# sensor.net
KiCad netlist of a schematic drawn in EAGLE
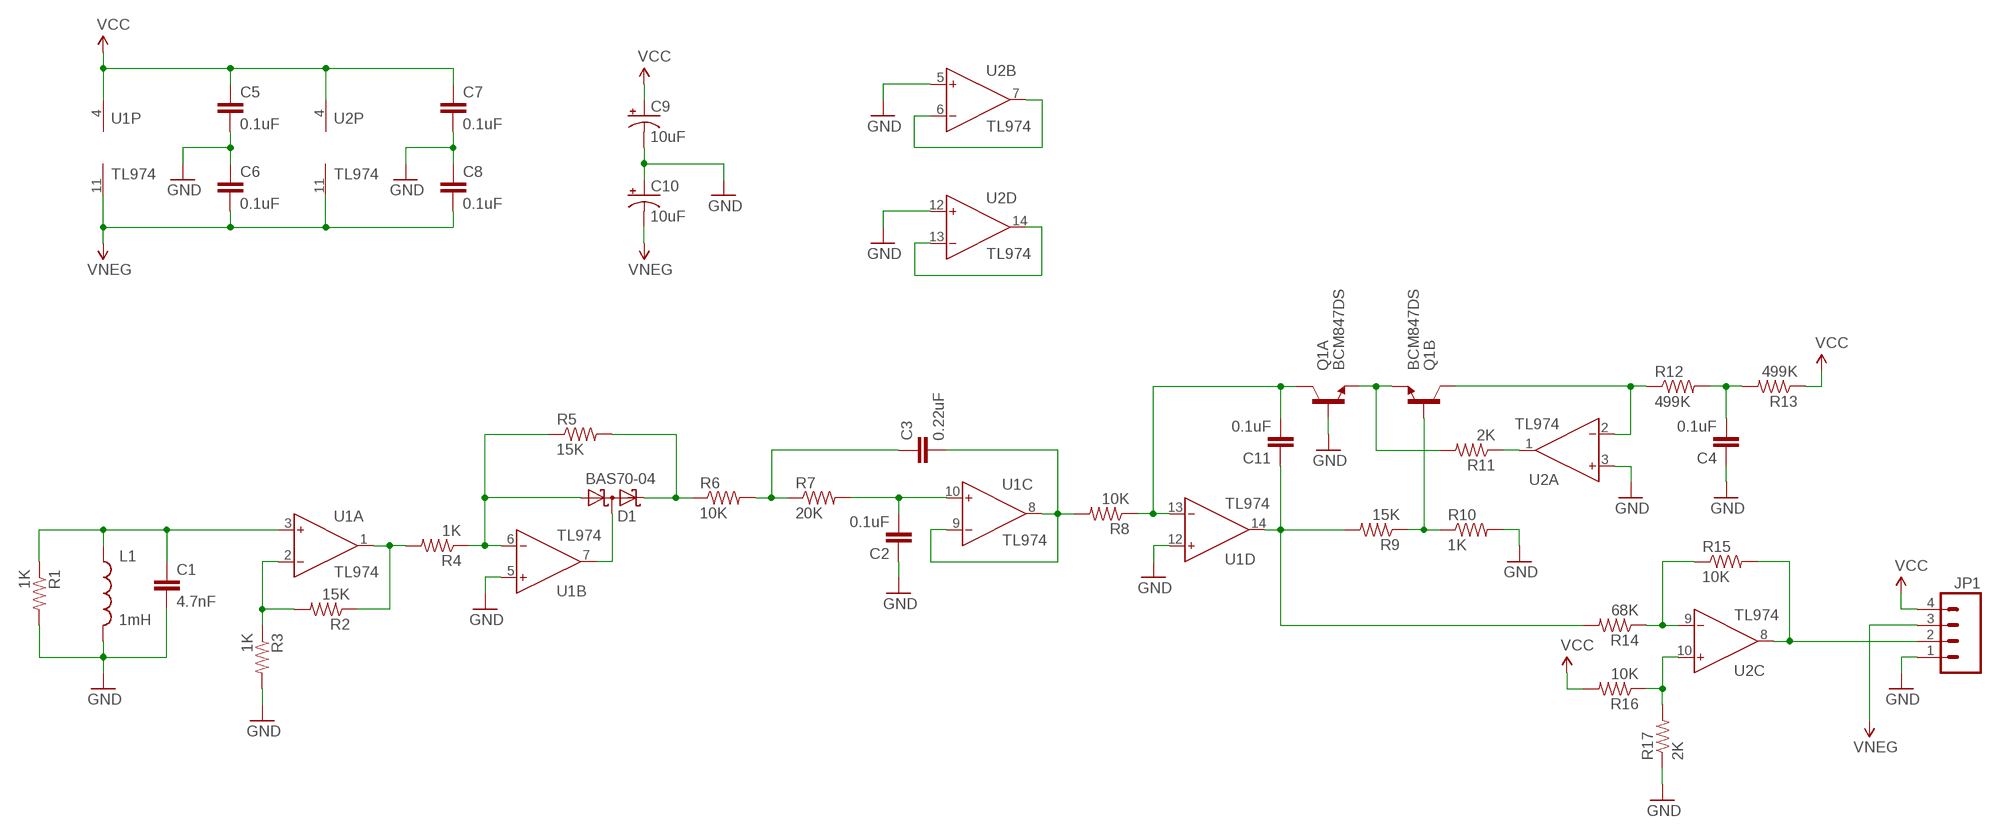
[diagram p0: schematic, sheet 1]

(export (version "E")
  (design (tool "Eeschema 10.0.6"))
  (components
    (comp (ref "C1")
      (value "4.7nF")
      (footprint "eagle-import:0805")
      (libsource (lib "eagle-import") (part "CAP0805"))
    )
    (comp (ref "C2")
      (value "0.1uF")
      (footprint "eagle-import:0805")
      (libsource (lib "eagle-import") (part "CAP0805"))
    )
    (comp (ref "C3")
      (value "0.22uF")
      (footprint "eagle-import:0805")
      (libsource (lib "eagle-import") (part "CAP0805"))
    )
    (comp (ref "C4")
      (value "0.1uF")
      (footprint "eagle-import:0805")
      (libsource (lib "eagle-import") (part "CAP0805"))
    )
    (comp (ref "C5")
      (value "0.1uF")
      (footprint "eagle-import:0805")
      (libsource (lib "eagle-import") (part "CAP0805"))
    )
    (comp (ref "C6")
      (value "0.1uF")
      (footprint "eagle-import:0805")
      (libsource (lib "eagle-import") (part "CAP0805"))
    )
    (comp (ref "C7")
      (value "0.1uF")
      (footprint "eagle-import:0805")
      (libsource (lib "eagle-import") (part "CAP0805"))
    )
    (comp (ref "C8")
      (value "0.1uF")
      (footprint "eagle-import:0805")
      (libsource (lib "eagle-import") (part "CAP0805"))
    )
    (comp (ref "C9")
      (value "10uF")
      (footprint "eagle-import:E2-4")
      (libsource (lib "eagle-import") (part "CPOL-USE2-4"))
    )
    (comp (ref "C10")
      (value "10uF")
      (footprint "eagle-import:E2-4")
      (libsource (lib "eagle-import") (part "CPOL-USE2-4"))
    )
    (comp (ref "C11")
      (value "0.1uF")
      (footprint "eagle-import:0805")
      (libsource (lib "eagle-import") (part "CAP0805"))
    )
    (comp (ref "D1")
      (value "BAS70-04")
      (footprint "eagle-import:SOT23")
      (libsource (lib "eagle-import") (part "BAS70-04"))
    )
    (comp (ref "JP1")
      (value "M04POLAR_LOCK")
      (footprint "eagle-import:MOLEX-1X4_LOCK")
      (libsource (lib "eagle-import") (part "M04POLAR_LOCK"))
    )
    (comp (ref "L1")
      (value "1mH")
      (footprint "eagle-import:RLB0912")
      (libsource (lib "eagle-import") (part "INDUCTORRLB0912"))
    )
    (comp (ref "Q1")
      (value "BCM847DS")
      (footprint "eagle-import:SOT-457")
      (libsource (lib "eagle-import") (part "BCM847DS"))
    )
    (comp (ref "R1")
      (value "1K")
      (footprint "eagle-import:0805")
      (libsource (lib "eagle-import") (part "RESISTOR0805-RES"))
    )
    (comp (ref "R2")
      (value "15K")
      (footprint "eagle-import:0805")
      (libsource (lib "eagle-import") (part "RESISTOR0805-RES"))
    )
    (comp (ref "R3")
      (value "1K")
      (footprint "eagle-import:0805")
      (libsource (lib "eagle-import") (part "RESISTOR0805-RES"))
    )
    (comp (ref "R4")
      (value "1K")
      (footprint "eagle-import:0805")
      (libsource (lib "eagle-import") (part "RESISTOR0805-RES"))
    )
    (comp (ref "R5")
      (value "15K")
      (footprint "eagle-import:0805")
      (libsource (lib "eagle-import") (part "RESISTOR0805-RES"))
    )
    (comp (ref "R6")
      (value "10K")
      (footprint "eagle-import:0805")
      (libsource (lib "eagle-import") (part "RESISTOR0805-RES"))
    )
    (comp (ref "R7")
      (value "20K")
      (footprint "eagle-import:0805")
      (libsource (lib "eagle-import") (part "RESISTOR0805-RES"))
    )
    (comp (ref "R8")
      (value "10K")
      (footprint "eagle-import:0805")
      (libsource (lib "eagle-import") (part "RESISTOR0805-RES"))
    )
    (comp (ref "R9")
      (value "15K")
      (footprint "eagle-import:0805")
      (libsource (lib "eagle-import") (part "RESISTOR0805-RES"))
    )
    (comp (ref "R10")
      (value "1K")
      (footprint "eagle-import:0805")
      (libsource (lib "eagle-import") (part "RESISTOR0805-RES"))
    )
    (comp (ref "R11")
      (value "2K")
      (footprint "eagle-import:0805")
      (libsource (lib "eagle-import") (part "RESISTOR0805-RES"))
    )
    (comp (ref "R12")
      (value "499K")
      (footprint "eagle-import:0805")
      (libsource (lib "eagle-import") (part "RESISTOR0805-RES"))
    )
    (comp (ref "R13")
      (value "499K")
      (footprint "eagle-import:0805")
      (libsource (lib "eagle-import") (part "RESISTOR0805-RES"))
    )
    (comp (ref "R14")
      (value "68K")
      (footprint "eagle-import:0805")
      (libsource (lib "eagle-import") (part "RESISTOR0805-RES"))
    )
    (comp (ref "R15")
      (value "10K")
      (footprint "eagle-import:0805")
      (libsource (lib "eagle-import") (part "RESISTOR0805-RES"))
    )
    (comp (ref "R16")
      (value "10K")
      (footprint "eagle-import:0805")
      (libsource (lib "eagle-import") (part "RESISTOR0805-RES"))
    )
    (comp (ref "R17")
      (value "2K")
      (footprint "eagle-import:0805")
      (libsource (lib "eagle-import") (part "RESISTOR0805-RES"))
    )
    (comp (ref "U1")
      (value "TL974")
      (footprint "eagle-import:SOIC-14")
      (libsource (lib "eagle-import") (part "TL974"))
    )
    (comp (ref "U2")
      (value "TL974")
      (footprint "eagle-import:SOIC-14")
      (libsource (lib "eagle-import") (part "TL974"))
    )
  )
  (nets
    (net (code "1") (name "GND") (class "Default")
      (node (ref "C1") (pin "2") (pinfunction "2_2") (pintype "passive"))
      (node (ref "C10") (pin "+") (pinfunction "+_+") (pintype "passive"))
      (node (ref "C2") (pin "1") (pinfunction "1_1") (pintype "passive"))
      (node (ref "C4") (pin "1") (pinfunction "1_1") (pintype "passive"))
      (node (ref "C5") (pin "2") (pinfunction "2_2") (pintype "passive"))
      (node (ref "C6") (pin "1") (pinfunction "1_1") (pintype "passive"))
      (node (ref "C7") (pin "2") (pinfunction "2_2") (pintype "passive"))
      (node (ref "C8") (pin "1") (pinfunction "1_1") (pintype "passive"))
      (node (ref "C9") (pin "-") (pinfunction "-_-") (pintype "passive"))
      (node (ref "JP1") (pin "1") (pinfunction "1_1") (pintype "passive"))
      (node (ref "L1") (pin "2") (pinfunction "2_2") (pintype "passive"))
      (node (ref "Q1") (pin "2") (pinfunction "B_2") (pintype "passive"))
      (node (ref "R1") (pin "2") (pinfunction "2_2") (pintype "passive"))
      (node (ref "R10") (pin "2") (pinfunction "2_2") (pintype "passive"))
      (node (ref "R17") (pin "1") (pinfunction "1_1") (pintype "passive"))
      (node (ref "R3") (pin "2") (pinfunction "2_2") (pintype "passive"))
      (node (ref "U1") (pin "12") (pinfunction "IN+_12") (pintype "input"))
      (node (ref "U1") (pin "5") (pinfunction "IN+_5") (pintype "input"))
      (node (ref "U2") (pin "12") (pinfunction "IN+_12") (pintype "input"))
      (node (ref "U2") (pin "3") (pinfunction "IN+_3") (pintype "input"))
      (node (ref "U2") (pin "5") (pinfunction "IN+_5") (pintype "input"))
    )
    (net (code "2") (name "Net-(C3-Pad1)") (class "Default")
      (node (ref "C3") (pin "1") (pinfunction "1_1") (pintype "passive"))
      (node (ref "R6") (pin "2") (pinfunction "2_2") (pintype "passive"))
      (node (ref "R7") (pin "1") (pinfunction "1_1") (pintype "passive"))
    )
    (net (code "3") (name "Net-(C4-Pad2)") (class "Default")
      (node (ref "C4") (pin "2") (pinfunction "2_2") (pintype "passive"))
      (node (ref "R12") (pin "2") (pinfunction "2_2") (pintype "passive"))
      (node (ref "R13") (pin "2") (pinfunction "2_2") (pintype "passive"))
    )
    (net (code "4") (name "Net-(D1-A1)") (class "Default")
      (node (ref "D1") (pin "1") (pinfunction "A1_1") (pintype "passive"))
      (node (ref "R4") (pin "1") (pinfunction "1_1") (pintype "passive"))
      (node (ref "R5") (pin "1") (pinfunction "1_1") (pintype "passive"))
      (node (ref "U1") (pin "6") (pinfunction "IN-_6") (pintype "input"))
    )
    (net (code "5") (name "Net-(D1-C1A2)") (class "Default")
      (node (ref "D1") (pin "3") (pinfunction "C1A2_3") (pintype "passive"))
      (node (ref "U1") (pin "7") (pinfunction "OUT_7") (pintype "output"))
    )
    (net (code "6") (name "Net-(D1-C2)") (class "Default")
      (node (ref "D1") (pin "2") (pinfunction "C2_2") (pintype "passive"))
      (node (ref "R5") (pin "2") (pinfunction "2_2") (pintype "passive"))
      (node (ref "R6") (pin "1") (pinfunction "1_1") (pintype "passive"))
    )
    (net (code "7") (name "Net-(Q1A-C)") (class "Default")
      (node (ref "C11") (pin "2") (pinfunction "2_2") (pintype "passive"))
      (node (ref "Q1") (pin "6") (pinfunction "C_6") (pintype "passive"))
      (node (ref "R8") (pin "1") (pinfunction "1_1") (pintype "passive"))
      (node (ref "U1") (pin "13") (pinfunction "IN-_13") (pintype "input"))
    )
    (net (code "8") (name "Net-(Q1A-E)") (class "Default")
      (node (ref "Q1") (pin "1") (pinfunction "E_1") (pintype "passive"))
      (node (ref "Q1") (pin "4") (pinfunction "E_4") (pintype "passive"))
      (node (ref "R11") (pin "2") (pinfunction "2_2") (pintype "passive"))
    )
    (net (code "9") (name "Net-(Q1B-B)") (class "Default")
      (node (ref "Q1") (pin "5") (pinfunction "B_5") (pintype "passive"))
      (node (ref "R10") (pin "1") (pinfunction "1_1") (pintype "passive"))
      (node (ref "R9") (pin "1") (pinfunction "1_1") (pintype "passive"))
    )
    (net (code "10") (name "Net-(Q1B-C)") (class "Default")
      (node (ref "Q1") (pin "3") (pinfunction "C_3") (pintype "passive"))
      (node (ref "R12") (pin "1") (pinfunction "1_1") (pintype "passive"))
      (node (ref "U2") (pin "2") (pinfunction "IN-_2") (pintype "input"))
    )
    (net (code "11") (name "Net-(U1A-IN+)") (class "Default")
      (node (ref "C1") (pin "1") (pinfunction "1_1") (pintype "passive"))
      (node (ref "L1") (pin "1") (pinfunction "1_1") (pintype "passive"))
      (node (ref "R1") (pin "1") (pinfunction "1_1") (pintype "passive"))
      (node (ref "U1") (pin "3") (pinfunction "IN+_3") (pintype "input"))
    )
    (net (code "12") (name "Net-(U1A-IN-)") (class "Default")
      (node (ref "R2") (pin "2") (pinfunction "2_2") (pintype "passive"))
      (node (ref "R3") (pin "1") (pinfunction "1_1") (pintype "passive"))
      (node (ref "U1") (pin "2") (pinfunction "IN-_2") (pintype "input"))
    )
    (net (code "13") (name "Net-(U1A-OUT)") (class "Default")
      (node (ref "R2") (pin "1") (pinfunction "1_1") (pintype "passive"))
      (node (ref "R4") (pin "2") (pinfunction "2_2") (pintype "passive"))
      (node (ref "U1") (pin "1") (pinfunction "OUT_1") (pintype "output"))
    )
    (net (code "14") (name "Net-(U1C-IN+)") (class "Default")
      (node (ref "C2") (pin "2") (pinfunction "2_2") (pintype "passive"))
      (node (ref "R7") (pin "2") (pinfunction "2_2") (pintype "passive"))
      (node (ref "U1") (pin "10") (pinfunction "IN+_10") (pintype "input"))
    )
    (net (code "15") (name "Net-(U1C-IN-)") (class "Default")
      (node (ref "C3") (pin "2") (pinfunction "2_2") (pintype "passive"))
      (node (ref "R8") (pin "2") (pinfunction "2_2") (pintype "passive"))
      (node (ref "U1") (pin "8") (pinfunction "OUT_8") (pintype "output"))
      (node (ref "U1") (pin "9") (pinfunction "IN-_9") (pintype "input"))
    )
    (net (code "16") (name "Net-(U1D-OUT)") (class "Default")
      (node (ref "C11") (pin "1") (pinfunction "1_1") (pintype "passive"))
      (node (ref "R14") (pin "2") (pinfunction "2_2") (pintype "passive"))
      (node (ref "R9") (pin "2") (pinfunction "2_2") (pintype "passive"))
      (node (ref "U1") (pin "14") (pinfunction "OUT_14") (pintype "output"))
    )
    (net (code "17") (name "Net-(U2A-OUT)") (class "Default")
      (node (ref "R11") (pin "1") (pinfunction "1_1") (pintype "passive"))
      (node (ref "U2") (pin "1") (pinfunction "OUT_1") (pintype "output"))
    )
    (net (code "18") (name "Net-(U2B-IN-)") (class "Default")
      (node (ref "U2") (pin "6") (pinfunction "IN-_6") (pintype "input"))
      (node (ref "U2") (pin "7") (pinfunction "OUT_7") (pintype "output"))
    )
    (net (code "19") (name "Net-(U2C-IN+)") (class "Default")
      (node (ref "R16") (pin "1") (pinfunction "1_1") (pintype "passive"))
      (node (ref "R17") (pin "2") (pinfunction "2_2") (pintype "passive"))
      (node (ref "U2") (pin "10") (pinfunction "IN+_10") (pintype "input"))
    )
    (net (code "20") (name "Net-(U2C-IN-)") (class "Default")
      (node (ref "R14") (pin "1") (pinfunction "1_1") (pintype "passive"))
      (node (ref "R15") (pin "1") (pinfunction "1_1") (pintype "passive"))
      (node (ref "U2") (pin "9") (pinfunction "IN-_9") (pintype "input"))
    )
    (net (code "21") (name "Net-(U2C-OUT)") (class "Default")
      (node (ref "JP1") (pin "2") (pinfunction "2_2") (pintype "passive"))
      (node (ref "R15") (pin "2") (pinfunction "2_2") (pintype "passive"))
      (node (ref "U2") (pin "8") (pinfunction "OUT_8") (pintype "output"))
    )
    (net (code "22") (name "Net-(U2D-IN-)") (class "Default")
      (node (ref "U2") (pin "13") (pinfunction "IN-_13") (pintype "input"))
      (node (ref "U2") (pin "14") (pinfunction "OUT_14") (pintype "output"))
    )
    (net (code "23") (name "VCC") (class "Default")
      (node (ref "C5") (pin "1") (pinfunction "1_1") (pintype "passive"))
      (node (ref "C7") (pin "1") (pinfunction "1_1") (pintype "passive"))
      (node (ref "C9") (pin "+") (pinfunction "+_+") (pintype "passive"))
      (node (ref "JP1") (pin "4") (pinfunction "4_4") (pintype "passive"))
      (node (ref "R13") (pin "1") (pinfunction "1_1") (pintype "passive"))
      (node (ref "R16") (pin "2") (pinfunction "2_2") (pintype "passive"))
      (node (ref "U1") (pin "4") (pinfunction "V+_4") (pintype "power_in"))
      (node (ref "U2") (pin "4") (pinfunction "V+_4") (pintype "power_in"))
    )
    (net (code "24") (name "VNEG") (class "Default")
      (node (ref "C10") (pin "-") (pinfunction "-_-") (pintype "passive"))
      (node (ref "C6") (pin "2") (pinfunction "2_2") (pintype "passive"))
      (node (ref "C8") (pin "2") (pinfunction "2_2") (pintype "passive"))
      (node (ref "JP1") (pin "3") (pinfunction "3_3") (pintype "passive"))
      (node (ref "U1") (pin "11") (pinfunction "V-_11") (pintype "power_in"))
      (node (ref "U2") (pin "11") (pinfunction "V-_11") (pintype "power_in"))
    )
  )
)
